# Breakout_v1.net
KiCad netlist of a schematic drawn in EAGLE
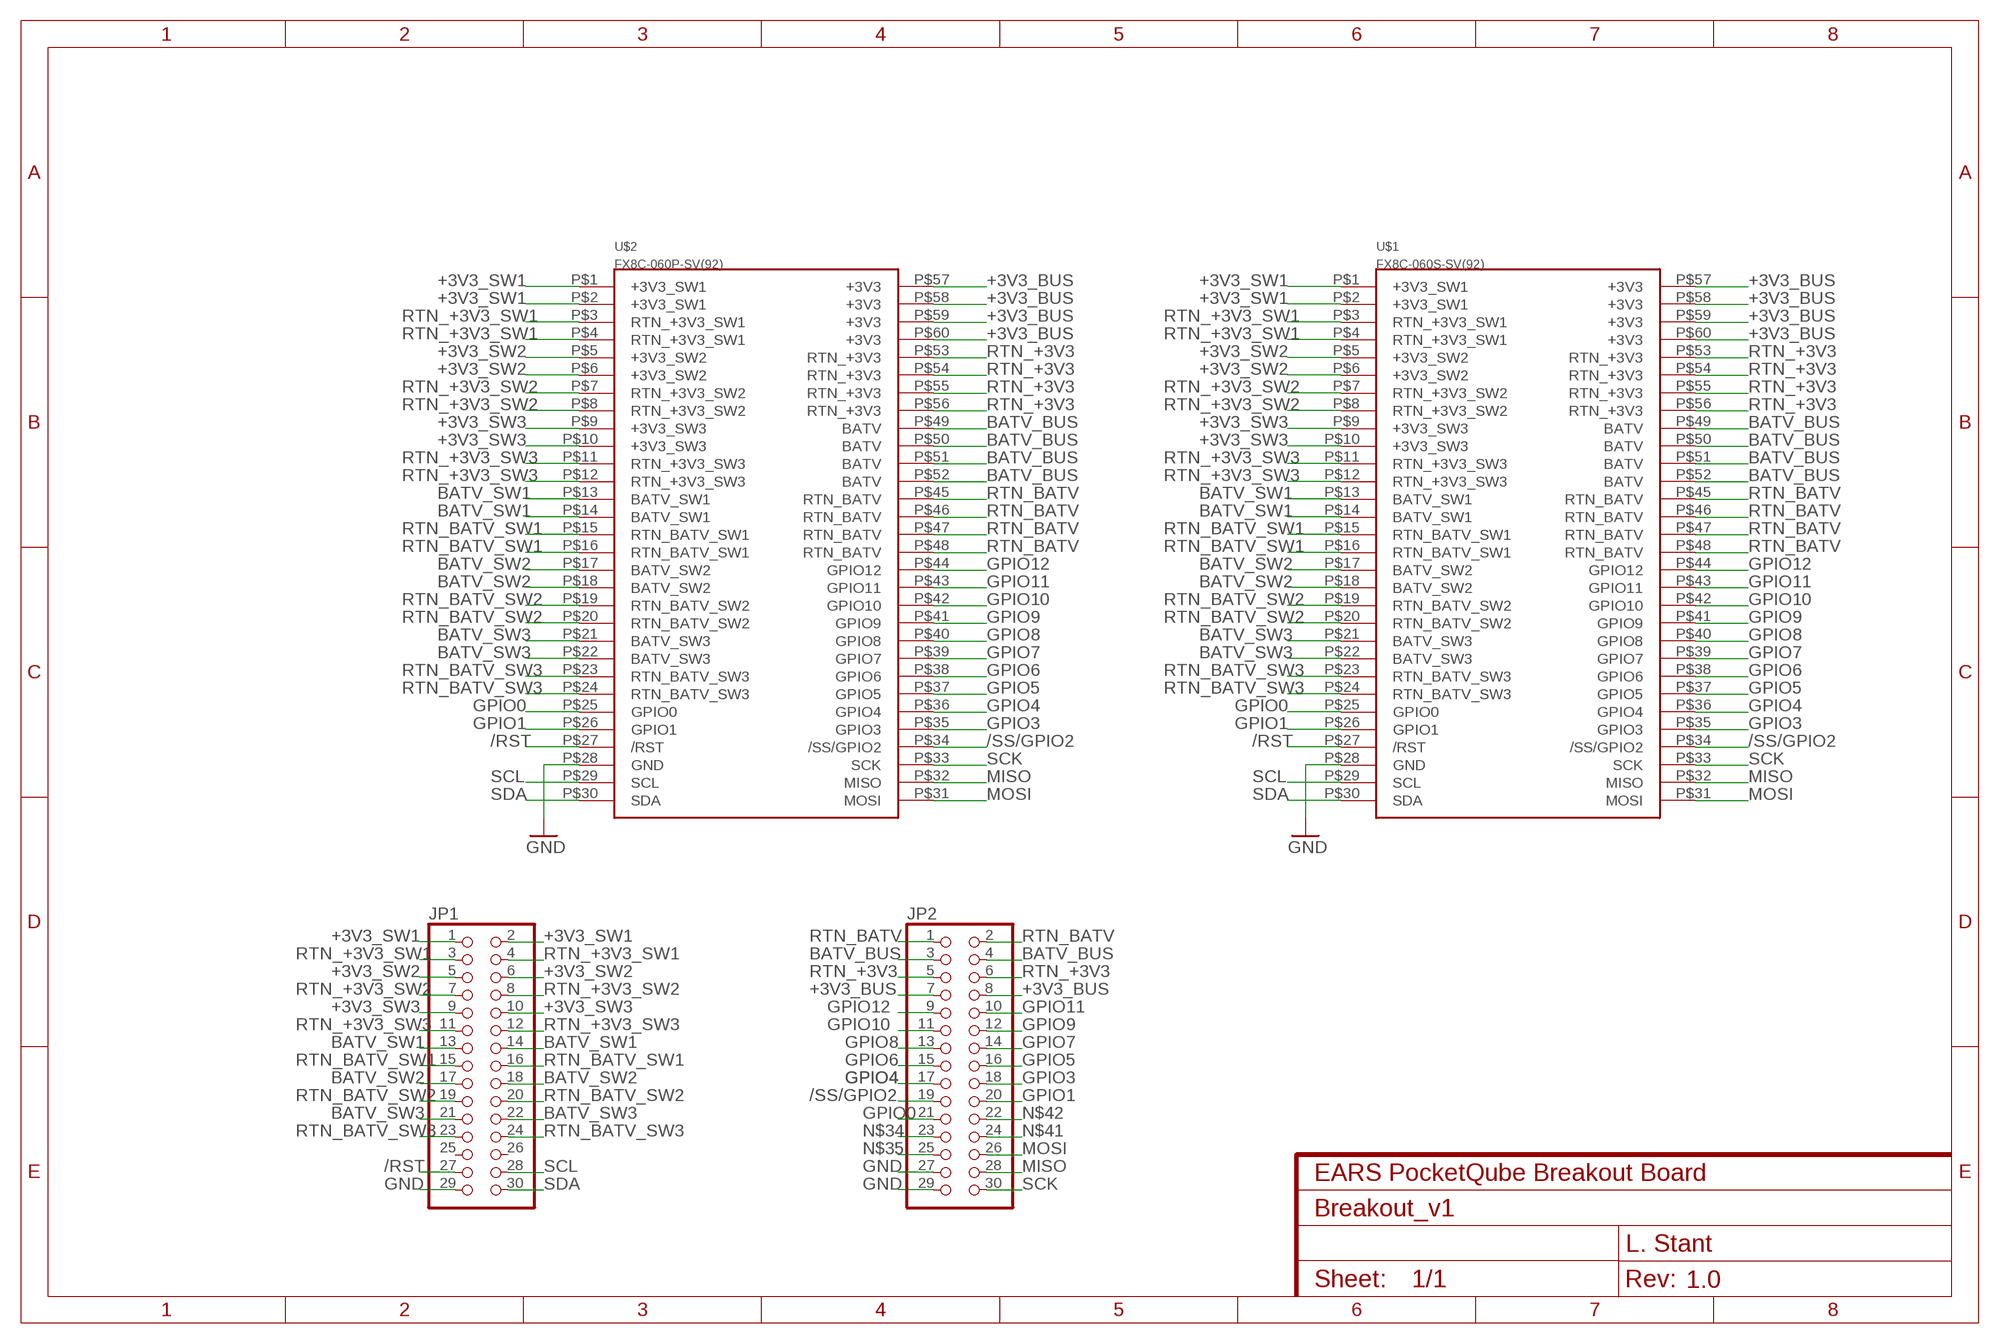
[diagram p0: schematic, sheet 1]

(export (version "E")
  (design (tool "Eeschema 10.0.6"))
  (components
    (comp (ref "JP1")
      (value "PINHD-2X15")
      (footprint "eagle-import:2X15")
      (libsource (lib "eagle-import") (part "PINHD-2X15"))
    )
    (comp (ref "JP2")
      (value "PINHD-2X15")
      (footprint "eagle-import:2X15")
      (libsource (lib "eagle-import") (part "PINHD-2X15"))
    )
    (comp (ref "U$1")
      (value "FX8C-060S-SV(92)")
      (footprint "eagle-import:FX8C-060S-SV(92)")
      (libsource (lib "eagle-import") (part "FX8C-060S-SV(92)"))
    )
    (comp (ref "U$2")
      (value "FX8C-060P-SV(92)")
      (footprint "eagle-import:FX8C-060P-SV(92)")
      (libsource (lib "eagle-import") (part "FX8C-060P-SV(92)"))
    )
  )
  (nets
    (net (code "1") (name "/+3V3_BUS") (class "Default")
      (node (ref "JP2") (pin "7") (pinfunction "7_7") (pintype "passive"))
      (node (ref "JP2") (pin "8") (pinfunction "8_8") (pintype "passive"))
      (node (ref "U$1") (pin "P$57") (pinfunction "+3V3_P$57") (pintype "power_in"))
      (node (ref "U$1") (pin "P$58") (pinfunction "+3V3_P$58") (pintype "power_in"))
      (node (ref "U$1") (pin "P$59") (pinfunction "+3V3_P$59") (pintype "power_in"))
      (node (ref "U$1") (pin "P$60") (pinfunction "+3V3_P$60") (pintype "power_in"))
      (node (ref "U$2") (pin "P$57") (pinfunction "+3V3_P$57") (pintype "power_in"))
      (node (ref "U$2") (pin "P$58") (pinfunction "+3V3_P$58") (pintype "power_in"))
      (node (ref "U$2") (pin "P$59") (pinfunction "+3V3_P$59") (pintype "power_in"))
      (node (ref "U$2") (pin "P$60") (pinfunction "+3V3_P$60") (pintype "power_in"))
    )
    (net (code "2") (name "/+3V3_SW1") (class "Default")
      (node (ref "JP1") (pin "1") (pinfunction "1_1") (pintype "passive"))
      (node (ref "JP1") (pin "2") (pinfunction "2_2") (pintype "passive"))
      (node (ref "U$1") (pin "P$1") (pinfunction "+3V3_SW1_P$1") (pintype "power_in"))
      (node (ref "U$1") (pin "P$2") (pinfunction "+3V3_SW1_P$2") (pintype "power_in"))
      (node (ref "U$2") (pin "P$1") (pinfunction "+3V3_SW1_P$1") (pintype "power_in"))
      (node (ref "U$2") (pin "P$2") (pinfunction "+3V3_SW1_P$2") (pintype "power_in"))
    )
    (net (code "3") (name "/+3V3_SW2") (class "Default")
      (node (ref "JP1") (pin "5") (pinfunction "5_5") (pintype "passive"))
      (node (ref "JP1") (pin "6") (pinfunction "6_6") (pintype "passive"))
      (node (ref "U$1") (pin "P$5") (pinfunction "+3V3_SW2_P$5") (pintype "power_in"))
      (node (ref "U$1") (pin "P$6") (pinfunction "+3V3_SW2_P$6") (pintype "power_in"))
      (node (ref "U$2") (pin "P$5") (pinfunction "+3V3_SW2_P$5") (pintype "power_in"))
      (node (ref "U$2") (pin "P$6") (pinfunction "+3V3_SW2_P$6") (pintype "power_in"))
    )
    (net (code "4") (name "/+3V3_SW3") (class "Default")
      (node (ref "JP1") (pin "10") (pinfunction "10_10") (pintype "passive"))
      (node (ref "JP1") (pin "9") (pinfunction "9_9") (pintype "passive"))
      (node (ref "U$1") (pin "P$10") (pinfunction "+3V3_SW3_P$10") (pintype "power_in"))
      (node (ref "U$1") (pin "P$9") (pinfunction "+3V3_SW3_P$9") (pintype "power_in"))
      (node (ref "U$2") (pin "P$10") (pinfunction "+3V3_SW3_P$10") (pintype "power_in"))
      (node (ref "U$2") (pin "P$9") (pinfunction "+3V3_SW3_P$9") (pintype "power_in"))
    )
    (net (code "5") (name "/BATV_BUS") (class "Default")
      (node (ref "JP2") (pin "3") (pinfunction "3_3") (pintype "passive"))
      (node (ref "JP2") (pin "4") (pinfunction "4_4") (pintype "passive"))
      (node (ref "U$1") (pin "P$49") (pinfunction "BATV_P$49") (pintype "power_in"))
      (node (ref "U$1") (pin "P$50") (pinfunction "BATV_P$50") (pintype "power_in"))
      (node (ref "U$1") (pin "P$51") (pinfunction "BATV_P$51") (pintype "power_in"))
      (node (ref "U$1") (pin "P$52") (pinfunction "BATV_P$52") (pintype "power_in"))
      (node (ref "U$2") (pin "P$49") (pinfunction "BATV_P$49") (pintype "power_in"))
      (node (ref "U$2") (pin "P$50") (pinfunction "BATV_P$50") (pintype "power_in"))
      (node (ref "U$2") (pin "P$51") (pinfunction "BATV_P$51") (pintype "power_in"))
      (node (ref "U$2") (pin "P$52") (pinfunction "BATV_P$52") (pintype "power_in"))
    )
    (net (code "6") (name "/BATV_SW1") (class "Default")
      (node (ref "JP1") (pin "13") (pinfunction "13_13") (pintype "passive"))
      (node (ref "JP1") (pin "14") (pinfunction "14_14") (pintype "passive"))
      (node (ref "U$1") (pin "P$13") (pinfunction "BATV_SW1_P$13") (pintype "power_in"))
      (node (ref "U$1") (pin "P$14") (pinfunction "BATV_SW1_P$14") (pintype "power_in"))
      (node (ref "U$2") (pin "P$13") (pinfunction "BATV_SW1_P$13") (pintype "power_in"))
      (node (ref "U$2") (pin "P$14") (pinfunction "BATV_SW1_P$14") (pintype "power_in"))
    )
    (net (code "7") (name "/BATV_SW2") (class "Default")
      (node (ref "JP1") (pin "17") (pinfunction "17_17") (pintype "passive"))
      (node (ref "JP1") (pin "18") (pinfunction "18_18") (pintype "passive"))
      (node (ref "U$1") (pin "P$17") (pinfunction "BATV_SW2_P$17") (pintype "power_in"))
      (node (ref "U$1") (pin "P$18") (pinfunction "BATV_SW2_P$18") (pintype "power_in"))
      (node (ref "U$2") (pin "P$17") (pinfunction "BATV_SW2_P$17") (pintype "power_in"))
      (node (ref "U$2") (pin "P$18") (pinfunction "BATV_SW2_P$18") (pintype "power_in"))
    )
    (net (code "8") (name "/BATV_SW3") (class "Default")
      (node (ref "JP1") (pin "21") (pinfunction "21_21") (pintype "passive"))
      (node (ref "JP1") (pin "22") (pinfunction "22_22") (pintype "passive"))
      (node (ref "U$1") (pin "P$21") (pinfunction "BATV_SW3_P$21") (pintype "power_in"))
      (node (ref "U$1") (pin "P$22") (pinfunction "BATV_SW3_P$22") (pintype "power_in"))
      (node (ref "U$2") (pin "P$21") (pinfunction "BATV_SW3_P$21") (pintype "power_in"))
      (node (ref "U$2") (pin "P$22") (pinfunction "BATV_SW3_P$22") (pintype "power_in"))
    )
    (net (code "9") (name "/GPIO0") (class "Default")
      (node (ref "JP2") (pin "21") (pinfunction "21_21") (pintype "passive"))
      (node (ref "U$1") (pin "P$25") (pinfunction "GPIO0_P$25") (pintype "bidirectional"))
      (node (ref "U$2") (pin "P$25") (pinfunction "GPIO0_P$25") (pintype "bidirectional"))
    )
    (net (code "10") (name "/GPIO1") (class "Default")
      (node (ref "JP2") (pin "20") (pinfunction "20_20") (pintype "passive"))
      (node (ref "U$1") (pin "P$26") (pinfunction "GPIO1_P$26") (pintype "bidirectional"))
      (node (ref "U$2") (pin "P$26") (pinfunction "GPIO1_P$26") (pintype "bidirectional"))
    )
    (net (code "11") (name "/GPIO3") (class "Default")
      (node (ref "JP2") (pin "18") (pinfunction "18_18") (pintype "passive"))
      (node (ref "U$1") (pin "P$35") (pinfunction "GPIO3_P$35") (pintype "bidirectional"))
      (node (ref "U$2") (pin "P$35") (pinfunction "GPIO3_P$35") (pintype "bidirectional"))
    )
    (net (code "12") (name "/GPIO4") (class "Default")
      (node (ref "JP2") (pin "17") (pinfunction "17_17") (pintype "passive"))
      (node (ref "U$1") (pin "P$36") (pinfunction "GPIO4_P$36") (pintype "bidirectional"))
      (node (ref "U$2") (pin "P$36") (pinfunction "GPIO4_P$36") (pintype "bidirectional"))
    )
    (net (code "13") (name "/GPIO5") (class "Default")
      (node (ref "JP2") (pin "16") (pinfunction "16_16") (pintype "passive"))
      (node (ref "U$1") (pin "P$37") (pinfunction "GPIO5_P$37") (pintype "bidirectional"))
      (node (ref "U$2") (pin "P$37") (pinfunction "GPIO5_P$37") (pintype "bidirectional"))
    )
    (net (code "14") (name "/GPIO6") (class "Default")
      (node (ref "JP2") (pin "15") (pinfunction "15_15") (pintype "passive"))
      (node (ref "U$1") (pin "P$38") (pinfunction "GPIO6_P$38") (pintype "bidirectional"))
      (node (ref "U$2") (pin "P$38") (pinfunction "GPIO6_P$38") (pintype "bidirectional"))
    )
    (net (code "15") (name "/GPIO7") (class "Default")
      (node (ref "JP2") (pin "14") (pinfunction "14_14") (pintype "passive"))
      (node (ref "U$1") (pin "P$39") (pinfunction "GPIO7_P$39") (pintype "bidirectional"))
      (node (ref "U$2") (pin "P$39") (pinfunction "GPIO7_P$39") (pintype "bidirectional"))
    )
    (net (code "16") (name "/GPIO8") (class "Default")
      (node (ref "JP2") (pin "13") (pinfunction "13_13") (pintype "passive"))
      (node (ref "U$1") (pin "P$40") (pinfunction "GPIO8_P$40") (pintype "bidirectional"))
      (node (ref "U$2") (pin "P$40") (pinfunction "GPIO8_P$40") (pintype "bidirectional"))
    )
    (net (code "17") (name "/GPIO9") (class "Default")
      (node (ref "JP2") (pin "12") (pinfunction "12_12") (pintype "passive"))
      (node (ref "U$1") (pin "P$41") (pinfunction "GPIO9_P$41") (pintype "bidirectional"))
      (node (ref "U$2") (pin "P$41") (pinfunction "GPIO9_P$41") (pintype "bidirectional"))
    )
    (net (code "18") (name "/GPIO10") (class "Default")
      (node (ref "JP2") (pin "11") (pinfunction "11_11") (pintype "passive"))
      (node (ref "U$1") (pin "P$42") (pinfunction "GPIO10_P$42") (pintype "bidirectional"))
      (node (ref "U$2") (pin "P$42") (pinfunction "GPIO10_P$42") (pintype "bidirectional"))
    )
    (net (code "19") (name "/GPIO11") (class "Default")
      (node (ref "JP2") (pin "10") (pinfunction "10_10") (pintype "passive"))
      (node (ref "U$1") (pin "P$43") (pinfunction "GPIO11_P$43") (pintype "bidirectional"))
      (node (ref "U$2") (pin "P$43") (pinfunction "GPIO11_P$43") (pintype "bidirectional"))
    )
    (net (code "20") (name "/GPIO12") (class "Default")
      (node (ref "JP2") (pin "9") (pinfunction "9_9") (pintype "passive"))
      (node (ref "U$1") (pin "P$44") (pinfunction "GPIO12_P$44") (pintype "bidirectional"))
      (node (ref "U$2") (pin "P$44") (pinfunction "GPIO12_P$44") (pintype "bidirectional"))
    )
    (net (code "21") (name "/MISO") (class "Default")
      (node (ref "JP2") (pin "28") (pinfunction "28_28") (pintype "passive"))
      (node (ref "U$1") (pin "P$32") (pinfunction "MISO_P$32") (pintype "bidirectional"))
      (node (ref "U$2") (pin "P$32") (pinfunction "MISO_P$32") (pintype "bidirectional"))
    )
    (net (code "22") (name "/MOSI") (class "Default")
      (node (ref "JP2") (pin "26") (pinfunction "26_26") (pintype "passive"))
      (node (ref "U$1") (pin "P$31") (pinfunction "MOSI_P$31") (pintype "bidirectional"))
      (node (ref "U$2") (pin "P$31") (pinfunction "MOSI_P$31") (pintype "bidirectional"))
    )
    (net (code "23") (name "/N$34") (class "Default")
      (node (ref "JP2") (pin "23") (pinfunction "23_23") (pintype "passive"))
    )
    (net (code "24") (name "/N$35") (class "Default")
      (node (ref "JP2") (pin "25") (pinfunction "25_25") (pintype "passive"))
    )
    (net (code "25") (name "/N$41") (class "Default")
      (node (ref "JP2") (pin "24") (pinfunction "24_24") (pintype "passive"))
    )
    (net (code "26") (name "/N$42") (class "Default")
      (node (ref "JP2") (pin "22") (pinfunction "22_22") (pintype "passive"))
    )
    (net (code "27") (name "/RTN_+3V3") (class "Default")
      (node (ref "JP2") (pin "5") (pinfunction "5_5") (pintype "passive"))
      (node (ref "JP2") (pin "6") (pinfunction "6_6") (pintype "passive"))
      (node (ref "U$1") (pin "P$53") (pinfunction "RTN_+3V3_P$53") (pintype "power_in"))
      (node (ref "U$1") (pin "P$54") (pinfunction "RTN_+3V3_P$54") (pintype "power_in"))
      (node (ref "U$1") (pin "P$55") (pinfunction "RTN_+3V3_P$55") (pintype "power_in"))
      (node (ref "U$1") (pin "P$56") (pinfunction "RTN_+3V3_P$56") (pintype "power_in"))
      (node (ref "U$2") (pin "P$53") (pinfunction "RTN_+3V3_P$53") (pintype "power_in"))
      (node (ref "U$2") (pin "P$54") (pinfunction "RTN_+3V3_P$54") (pintype "power_in"))
      (node (ref "U$2") (pin "P$55") (pinfunction "RTN_+3V3_P$55") (pintype "power_in"))
      (node (ref "U$2") (pin "P$56") (pinfunction "RTN_+3V3_P$56") (pintype "power_in"))
    )
    (net (code "28") (name "/RTN_+3V3_SW1") (class "Default")
      (node (ref "JP1") (pin "3") (pinfunction "3_3") (pintype "passive"))
      (node (ref "JP1") (pin "4") (pinfunction "4_4") (pintype "passive"))
      (node (ref "U$1") (pin "P$3") (pinfunction "RTN_+3V3_SW1_P$3") (pintype "power_in"))
      (node (ref "U$1") (pin "P$4") (pinfunction "RTN_+3V3_SW1_P$4") (pintype "power_in"))
      (node (ref "U$2") (pin "P$3") (pinfunction "RTN_+3V3_SW1_P$3") (pintype "power_in"))
      (node (ref "U$2") (pin "P$4") (pinfunction "RTN_+3V3_SW1_P$4") (pintype "power_in"))
    )
    (net (code "29") (name "/RTN_+3V3_SW2") (class "Default")
      (node (ref "JP1") (pin "7") (pinfunction "7_7") (pintype "passive"))
      (node (ref "JP1") (pin "8") (pinfunction "8_8") (pintype "passive"))
      (node (ref "U$1") (pin "P$7") (pinfunction "RTN_+3V3_SW2_P$7") (pintype "power_in"))
      (node (ref "U$1") (pin "P$8") (pinfunction "RTN_+3V3_SW2_P$8") (pintype "power_in"))
      (node (ref "U$2") (pin "P$7") (pinfunction "RTN_+3V3_SW2_P$7") (pintype "power_in"))
      (node (ref "U$2") (pin "P$8") (pinfunction "RTN_+3V3_SW2_P$8") (pintype "power_in"))
    )
    (net (code "30") (name "/RTN_+3V3_SW3") (class "Default")
      (node (ref "JP1") (pin "11") (pinfunction "11_11") (pintype "passive"))
      (node (ref "JP1") (pin "12") (pinfunction "12_12") (pintype "passive"))
      (node (ref "U$1") (pin "P$11") (pinfunction "RTN_+3V3_SW3_P$11") (pintype "power_in"))
      (node (ref "U$1") (pin "P$12") (pinfunction "RTN_+3V3_SW3_P$12") (pintype "power_in"))
      (node (ref "U$2") (pin "P$11") (pinfunction "RTN_+3V3_SW3_P$11") (pintype "power_in"))
      (node (ref "U$2") (pin "P$12") (pinfunction "RTN_+3V3_SW3_P$12") (pintype "power_in"))
    )
    (net (code "31") (name "/RTN_BATV") (class "Default")
      (node (ref "JP2") (pin "1") (pinfunction "1_1") (pintype "passive"))
      (node (ref "JP2") (pin "2") (pinfunction "2_2") (pintype "passive"))
      (node (ref "U$1") (pin "P$45") (pinfunction "RTN_BATV_P$45") (pintype "power_in"))
      (node (ref "U$1") (pin "P$46") (pinfunction "RTN_BATV_P$46") (pintype "power_in"))
      (node (ref "U$1") (pin "P$47") (pinfunction "RTN_BATV_P$47") (pintype "power_in"))
      (node (ref "U$1") (pin "P$48") (pinfunction "RTN_BATV_P$48") (pintype "power_in"))
      (node (ref "U$2") (pin "P$45") (pinfunction "RTN_BATV_P$45") (pintype "power_in"))
      (node (ref "U$2") (pin "P$46") (pinfunction "RTN_BATV_P$46") (pintype "power_in"))
      (node (ref "U$2") (pin "P$47") (pinfunction "RTN_BATV_P$47") (pintype "power_in"))
      (node (ref "U$2") (pin "P$48") (pinfunction "RTN_BATV_P$48") (pintype "power_in"))
    )
    (net (code "32") (name "/RTN_BATV_SW1") (class "Default")
      (node (ref "JP1") (pin "15") (pinfunction "15_15") (pintype "passive"))
      (node (ref "JP1") (pin "16") (pinfunction "16_16") (pintype "passive"))
      (node (ref "U$1") (pin "P$15") (pinfunction "RTN_BATV_SW1_P$15") (pintype "power_in"))
      (node (ref "U$1") (pin "P$16") (pinfunction "RTN_BATV_SW1_P$16") (pintype "power_in"))
      (node (ref "U$2") (pin "P$15") (pinfunction "RTN_BATV_SW1_P$15") (pintype "power_in"))
      (node (ref "U$2") (pin "P$16") (pinfunction "RTN_BATV_SW1_P$16") (pintype "power_in"))
    )
    (net (code "33") (name "/RTN_BATV_SW2") (class "Default")
      (node (ref "JP1") (pin "19") (pinfunction "19_19") (pintype "passive"))
      (node (ref "JP1") (pin "20") (pinfunction "20_20") (pintype "passive"))
      (node (ref "U$1") (pin "P$19") (pinfunction "RTN_BATV_SW2_P$19") (pintype "power_in"))
      (node (ref "U$1") (pin "P$20") (pinfunction "RTN_BATV_SW2_P$20") (pintype "power_in"))
      (node (ref "U$2") (pin "P$19") (pinfunction "RTN_BATV_SW2_P$19") (pintype "power_in"))
      (node (ref "U$2") (pin "P$20") (pinfunction "RTN_BATV_SW2_P$20") (pintype "power_in"))
    )
    (net (code "34") (name "/RTN_BATV_SW3") (class "Default")
      (node (ref "JP1") (pin "23") (pinfunction "23_23") (pintype "passive"))
      (node (ref "JP1") (pin "24") (pinfunction "24_24") (pintype "passive"))
      (node (ref "U$1") (pin "P$23") (pinfunction "RTN_BATV_SW3_P$23") (pintype "power_in"))
      (node (ref "U$1") (pin "P$24") (pinfunction "RTN_BATV_SW3_P$24") (pintype "power_in"))
      (node (ref "U$2") (pin "P$23") (pinfunction "RTN_BATV_SW3_P$23") (pintype "power_in"))
      (node (ref "U$2") (pin "P$24") (pinfunction "RTN_BATV_SW3_P$24") (pintype "power_in"))
    )
    (net (code "35") (name "/SCK") (class "Default")
      (node (ref "JP2") (pin "30") (pinfunction "30_30") (pintype "passive"))
      (node (ref "U$1") (pin "P$33") (pinfunction "SCK_P$33") (pintype "bidirectional"))
      (node (ref "U$2") (pin "P$33") (pinfunction "SCK_P$33") (pintype "bidirectional"))
    )
    (net (code "36") (name "/SCL") (class "Default")
      (node (ref "JP1") (pin "28") (pinfunction "28_28") (pintype "passive"))
      (node (ref "U$1") (pin "P$29") (pinfunction "SCL_P$29") (pintype "bidirectional"))
      (node (ref "U$2") (pin "P$29") (pinfunction "SCL_P$29") (pintype "bidirectional"))
    )
    (net (code "37") (name "/SDA") (class "Default")
      (node (ref "JP1") (pin "30") (pinfunction "30_30") (pintype "passive"))
      (node (ref "U$1") (pin "P$30") (pinfunction "SDA_P$30") (pintype "bidirectional"))
      (node (ref "U$2") (pin "P$30") (pinfunction "SDA_P$30") (pintype "bidirectional"))
    )
    (net (code "38") (name "/{slash}RST") (class "Default")
      (node (ref "JP1") (pin "27") (pinfunction "27_27") (pintype "passive"))
      (node (ref "U$1") (pin "P$27") (pinfunction "/RST_P$27") (pintype "bidirectional"))
      (node (ref "U$2") (pin "P$27") (pinfunction "/RST_P$27") (pintype "bidirectional"))
    )
    (net (code "39") (name "/{slash}SS{slash}GPIO2") (class "Default")
      (node (ref "JP2") (pin "19") (pinfunction "19_19") (pintype "passive"))
      (node (ref "U$1") (pin "P$34") (pinfunction "/SS/GPIO2_P$34") (pintype "bidirectional"))
      (node (ref "U$2") (pin "P$34") (pinfunction "/SS/GPIO2_P$34") (pintype "bidirectional"))
    )
    (net (code "40") (name "GND") (class "Default")
      (node (ref "JP1") (pin "29") (pinfunction "29_29") (pintype "passive"))
      (node (ref "JP2") (pin "27") (pinfunction "27_27") (pintype "passive"))
      (node (ref "JP2") (pin "29") (pinfunction "29_29") (pintype "passive"))
      (node (ref "U$1") (pin "P$28") (pinfunction "GND_P$28") (pintype "bidirectional"))
      (node (ref "U$2") (pin "P$28") (pinfunction "GND_P$28") (pintype "bidirectional"))
    )
    (net (code "41") (name "unconnected-(JP1-Pad25)") (class "Default")
      (node (ref "JP1") (pin "25") (pinfunction "25_25") (pintype "passive"))
    )
    (net (code "42") (name "unconnected-(JP1-Pad26)") (class "Default")
      (node (ref "JP1") (pin "26") (pinfunction "26_26") (pintype "passive"))
    )
  )
)
